# Shore_Power.net
KiCad netlist of a schematic drawn in Altium Designer
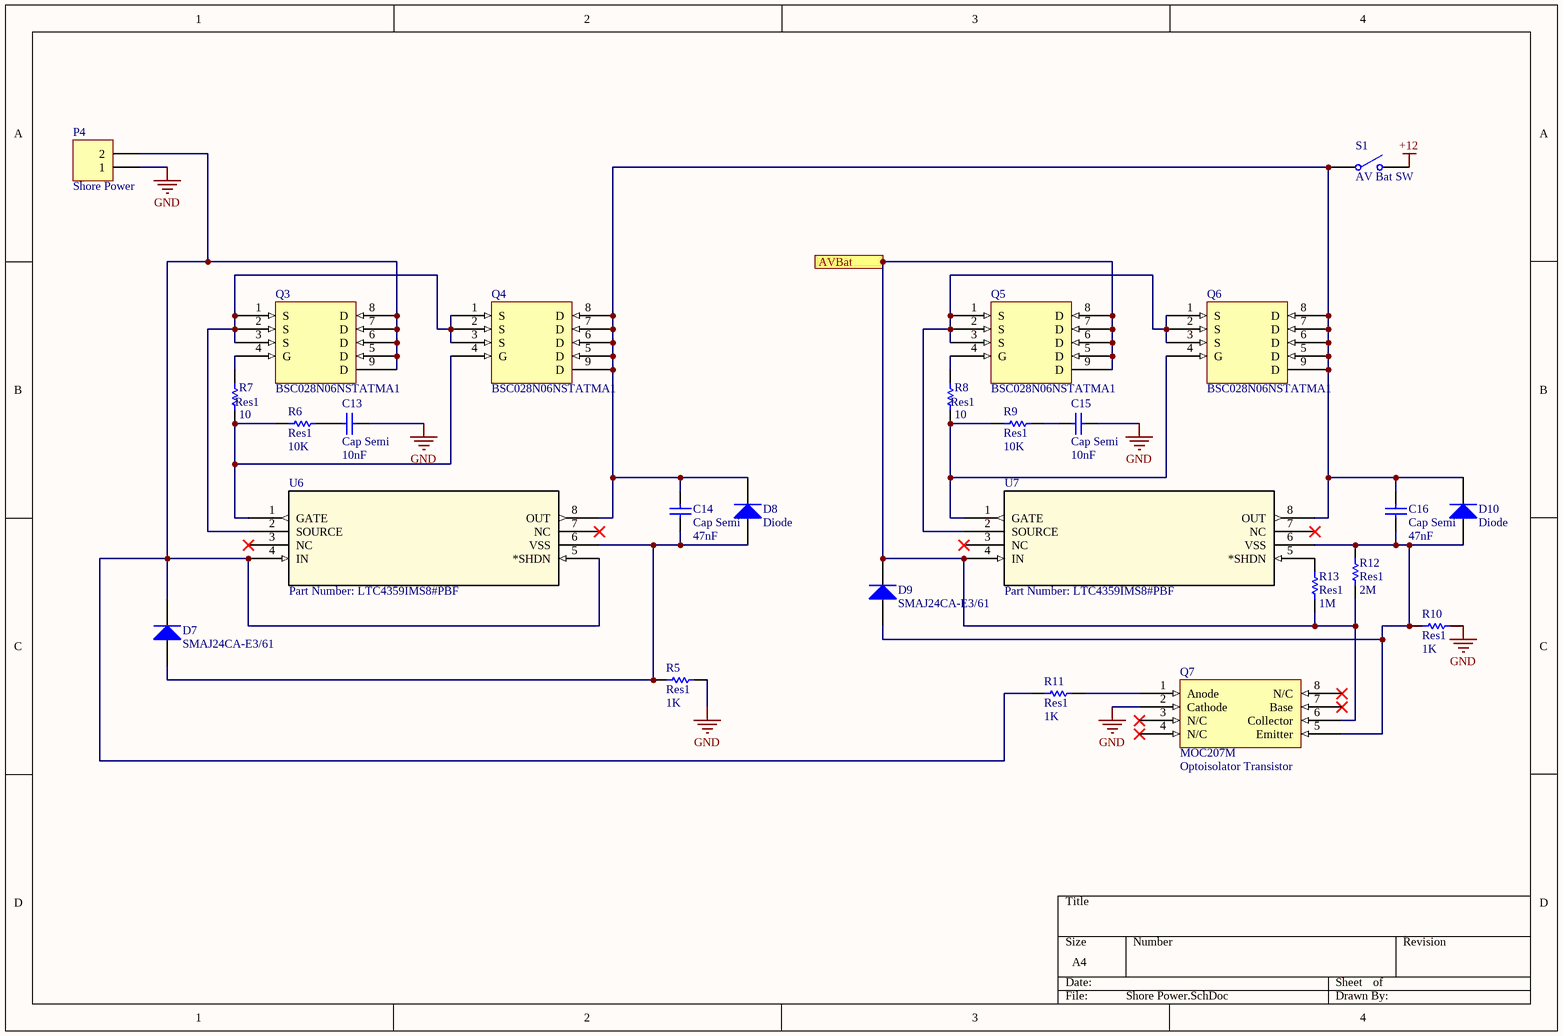
[diagram p0: Shore Power.SchDoc]

(export (version "E")
  (design (tool "Eeschema 10.0.6"))
  (components
    (comp (ref "C13")
      (value "Cap Semi")
      (footprint "C1206")
      (description "Capacitor (Semiconductor SIM Model)")
      (fields (field (name "ALTIUM_VALUE") "10nF") (field (name "PUBLISHER") "Altium Limited"))
      (libsource (lib "Miscellaneous Devices") (part "Cap Semi"))
    )
    (comp (ref "C14")
      (value "Cap Semi")
      (footprint "C1206")
      (description "Capacitor (Semiconductor SIM Model)")
      (fields (field (name "ALTIUM_VALUE") "47nF") (field (name "PUBLISHER") "Altium Limited"))
      (libsource (lib "Miscellaneous Devices") (part "Cap Semi"))
    )
    (comp (ref "C15")
      (value "Cap Semi")
      (footprint "C1206")
      (description "Capacitor (Semiconductor SIM Model)")
      (fields (field (name "ALTIUM_VALUE") "10nF") (field (name "PUBLISHER") "Altium Limited"))
      (libsource (lib "Miscellaneous Devices") (part "Cap Semi"))
    )
    (comp (ref "C16")
      (value "Cap Semi")
      (footprint "C1206")
      (description "Capacitor (Semiconductor SIM Model)")
      (fields (field (name "ALTIUM_VALUE") "47nF") (field (name "PUBLISHER") "Altium Limited"))
      (libsource (lib "Miscellaneous Devices") (part "Cap Semi"))
    )
    (comp (ref "D7")
      (value "SMAJ24CA-E3/61")
      (footprint "DIODE_DO-214AC")
      (description "Default Diode")
      (fields (field (name "PUBLISHER") "Altium Limited"))
      (libsource (lib "Miscellaneous Devices") (part "Diode"))
    )
    (comp (ref "D8")
      (value "Diode")
      (footprint "DIOM4427X27N")
      (description "Default Diode")
      (fields (field (name "PUBLISHER") "Altium Limited"))
      (libsource (lib "Miscellaneous Devices") (part "Diode"))
    )
    (comp (ref "D9")
      (value "SMAJ24CA-E3/61")
      (footprint "DIODE_DO-214AC")
      (description "Default Diode")
      (fields (field (name "PUBLISHER") "Altium Limited"))
      (libsource (lib "Miscellaneous Devices") (part "Diode"))
    )
    (comp (ref "D10")
      (value "Diode")
      (footprint "DIOM4427X27N")
      (description "Default Diode")
      (fields (field (name "PUBLISHER") "Altium Limited"))
      (libsource (lib "Miscellaneous Devices") (part "Diode"))
    )
    (comp (ref "P4")
      (value "Shore Power")
      (footprint "HDR1X2")
      (description "Header, 2-Pin")
      (fields (field (name "PUBLISHER") "Altium Limited"))
      (libsource (lib "Miscellaneous Connectors") (part "Header 2"))
    )
    (comp (ref "Q3")
      (value "BSC028N06NSTATMA1")
      (footprint "FDMS86101A")
      (description "MOSFET N-CH 100V 13A POWER56")
      (libsource (lib "FDMS86101A") (part "FDMS86101A"))
    )
    (comp (ref "Q4")
      (value "BSC028N06NSTATMA1")
      (footprint "FDMS86101A")
      (description "MOSFET N-CH 100V 13A POWER56")
      (libsource (lib "FDMS86101A") (part "FDMS86101A"))
    )
    (comp (ref "Q5")
      (value "BSC028N06NSTATMA1")
      (footprint "FDMS86101A")
      (description "MOSFET N-CH 100V 13A POWER56")
      (libsource (lib "FDMS86101A") (part "FDMS86101A"))
    )
    (comp (ref "Q6")
      (value "BSC028N06NSTATMA1")
      (footprint "FDMS86101A")
      (description "MOSFET N-CH 100V 13A POWER56")
      (libsource (lib "FDMS86101A") (part "FDMS86101A"))
    )
    (comp (ref "Q7")
      (value "MOC207M")
      (footprint "SOIC127P590X363-8N")
      (description "Optoisolator Transistor")
      (fields (field (name "DESC") "Optoisolator Transistor"))
      (libsource (lib "MOC207M") (part "MOC207M"))
    )
    (comp (ref "R5")
      (value "Res1")
      (footprint "STA_RMCF2512")
      (description "Resistor")
      (fields (field (name "ALTIUM_VALUE") "1K") (field (name "PUBLISHER") "Altium Limited"))
      (libsource (lib "Miscellaneous Devices") (part "Res1"))
    )
    (comp (ref "R6")
      (value "Res1")
      (footprint "6-0805_L")
      (description "Resistor")
      (fields (field (name "ALTIUM_VALUE") "10K") (field (name "PUBLISHER") "Altium Limited"))
      (libsource (lib "Miscellaneous Devices") (part "Res1"))
    )
    (comp (ref "R7")
      (value "Res1")
      (footprint "6-0805_L")
      (description "Resistor")
      (fields (field (name "ALTIUM_VALUE") "10") (field (name "PUBLISHER") "Altium Limited"))
      (libsource (lib "Miscellaneous Devices") (part "Res1"))
    )
    (comp (ref "R8")
      (value "Res1")
      (footprint "6-0805_L")
      (description "Resistor")
      (fields (field (name "ALTIUM_VALUE") "10") (field (name "PUBLISHER") "Altium Limited"))
      (libsource (lib "Miscellaneous Devices") (part "Res1"))
    )
    (comp (ref "R9")
      (value "Res1")
      (footprint "6-0805_L")
      (description "Resistor")
      (fields (field (name "ALTIUM_VALUE") "10K") (field (name "PUBLISHER") "Altium Limited"))
      (libsource (lib "Miscellaneous Devices") (part "Res1"))
    )
    (comp (ref "R10")
      (value "Res1")
      (footprint "STA_RMCF2512")
      (description "Resistor")
      (fields (field (name "ALTIUM_VALUE") "1K") (field (name "PUBLISHER") "Altium Limited"))
      (libsource (lib "Miscellaneous Devices") (part "Res1"))
    )
    (comp (ref "R11")
      (value "Res1")
      (footprint "STA_RMCF2512")
      (description "Resistor")
      (fields (field (name "ALTIUM_VALUE") "1K") (field (name "PUBLISHER") "Altium Limited"))
      (libsource (lib "Miscellaneous Devices") (part "Res1"))
    )
    (comp (ref "R12")
      (value "Res1")
      (footprint "J1-0603")
      (description "Resistor")
      (fields (field (name "ALTIUM_VALUE") "2M") (field (name "PUBLISHER") "Altium Limited"))
      (libsource (lib "Miscellaneous Devices") (part "Res1"))
    )
    (comp (ref "R13")
      (value "Res1")
      (footprint "J1-0603")
      (description "Resistor")
      (fields (field (name "ALTIUM_VALUE") "1M") (field (name "PUBLISHER") "Altium Limited"))
      (libsource (lib "Miscellaneous Devices") (part "Res1"))
    )
    (comp (ref "S1")
      (value "AV Bat SW")
      (footprint "SPST-2")
      (description "Single-Pole, Single-Throw Switch")
      (fields (field (name "PUBLISHER") "Altium Limited"))
      (libsource (lib "Miscellaneous Devices") (part "SW-SPST"))
    )
    (comp (ref "U6")
      (value "Part Number: LTC4359IMS8#PBF")
      (footprint "MSOP-8_MS")
      (description "No Description Available")
      (fields
        (field (name "MANUFACTURER_PART_NUMBER") "LTC4359IMS8#PBF")
        (field (name "COPYRIGHT") "Copyright (C) 2018 Accelerated Designs. All rights reserved")
      )
      (libsource (lib "LTC4359IMS8#PBF") (part "LTC4359IMS8#PBF"))
    )
    (comp (ref "U7")
      (value "Part Number: LTC4359IMS8#PBF")
      (footprint "MSOP-8_MS")
      (description "No Description Available")
      (fields
        (field (name "MANUFACTURER_PART_NUMBER") "LTC4359IMS8#PBF")
        (field (name "COPYRIGHT") "Copyright (C) 2018 Accelerated Designs. All rights reserved")
      )
      (libsource (lib "LTC4359IMS8#PBF") (part "LTC4359IMS8#PBF"))
    )
  )
  (nets
    (net (code "1") (name "+12") (class "Default")
      (node (ref "S1") (pin "2") (pinfunction "NO_2") (pintype "passive"))
    )
    (net (code "2") (name "/AVBat") (class "Default")
      (node (ref "D9") (pin "2") (pinfunction "K_2") (pintype "passive"))
      (node (ref "Q5") (pin "5") (pinfunction "D_5") (pintype "input"))
      (node (ref "Q5") (pin "6") (pinfunction "D_6") (pintype "input"))
      (node (ref "Q5") (pin "7") (pinfunction "D_7") (pintype "input"))
      (node (ref "Q5") (pin "8") (pinfunction "D_8") (pintype "input"))
      (node (ref "Q5") (pin "9") (pinfunction "D_9") (pintype "passive"))
      (node (ref "Q7") (pin "6") (pinfunction "Collector_6") (pintype "input"))
      (node (ref "R12") (pin "1") (pinfunction "1_1") (pintype "passive"))
      (node (ref "R13") (pin "2") (pinfunction "2_2") (pintype "passive"))
      (node (ref "U7") (pin "4") (pinfunction "IN_4") (pintype "input"))
    )
    (net (code "3") (name "GND") (class "Default")
      (node (ref "C13") (pin "1") (pinfunction "1_1") (pintype "passive"))
      (node (ref "C15") (pin "1") (pinfunction "1_1") (pintype "passive"))
      (node (ref "P4") (pin "1") (pinfunction "1_1") (pintype "passive"))
      (node (ref "Q7") (pin "2") (pinfunction "Cathode_2") (pintype "input"))
      (node (ref "R10") (pin "1") (pinfunction "1_1") (pintype "passive"))
      (node (ref "R5") (pin "1") (pinfunction "1_1") (pintype "passive"))
    )
    (net (code "4") (name "Net-(C13-Pad2)") (class "Default")
      (node (ref "C13") (pin "2") (pinfunction "2_2") (pintype "passive"))
      (node (ref "R6") (pin "2") (pinfunction "2_2") (pintype "passive"))
    )
    (net (code "5") (name "Net-(C15-Pad2)") (class "Default")
      (node (ref "C15") (pin "2") (pinfunction "2_2") (pintype "passive"))
      (node (ref "R9") (pin "2") (pinfunction "2_2") (pintype "passive"))
    )
    (net (code "6") (name "Net-(D7-A)") (class "Default")
      (node (ref "C14") (pin "2") (pinfunction "2_2") (pintype "passive"))
      (node (ref "D7") (pin "1") (pinfunction "A_1") (pintype "passive"))
      (node (ref "D8") (pin "1") (pinfunction "A_1") (pintype "passive"))
      (node (ref "R5") (pin "2") (pinfunction "2_2") (pintype "passive"))
      (node (ref "U6") (pin "6") (pinfunction "VSS_6") (pintype "power_in"))
    )
    (net (code "7") (name "Net-(D7-K)") (class "Default")
      (node (ref "D7") (pin "2") (pinfunction "K_2") (pintype "passive"))
      (node (ref "P4") (pin "2") (pinfunction "2_2") (pintype "passive"))
      (node (ref "Q3") (pin "5") (pinfunction "D_5") (pintype "input"))
      (node (ref "Q3") (pin "6") (pinfunction "D_6") (pintype "input"))
      (node (ref "Q3") (pin "7") (pinfunction "D_7") (pintype "input"))
      (node (ref "Q3") (pin "8") (pinfunction "D_8") (pintype "input"))
      (node (ref "Q3") (pin "9") (pinfunction "D_9") (pintype "passive"))
      (node (ref "R11") (pin "2") (pinfunction "2_2") (pintype "passive"))
      (node (ref "U6") (pin "4") (pinfunction "IN_4") (pintype "input"))
      (node (ref "U6") (pin "5") (pinfunction "*SHDN_5") (pintype "input"))
    )
    (net (code "8") (name "Net-(D10-A)") (class "Default")
      (node (ref "C16") (pin "2") (pinfunction "2_2") (pintype "passive"))
      (node (ref "D10") (pin "1") (pinfunction "A_1") (pintype "passive"))
      (node (ref "D9") (pin "1") (pinfunction "A_1") (pintype "passive"))
      (node (ref "Q7") (pin "5") (pinfunction "Emitter_5") (pintype "input"))
      (node (ref "R10") (pin "2") (pinfunction "2_2") (pintype "passive"))
      (node (ref "R12") (pin "2") (pinfunction "2_2") (pintype "passive"))
      (node (ref "U7") (pin "6") (pinfunction "VSS_6") (pintype "power_in"))
    )
    (net (code "9") (name "Net-(D10-K)") (class "Default")
      (node (ref "C14") (pin "1") (pinfunction "1_1") (pintype "passive"))
      (node (ref "C16") (pin "1") (pinfunction "1_1") (pintype "passive"))
      (node (ref "D10") (pin "2") (pinfunction "K_2") (pintype "passive"))
      (node (ref "D8") (pin "2") (pinfunction "K_2") (pintype "passive"))
      (node (ref "Q4") (pin "5") (pinfunction "D_5") (pintype "input"))
      (node (ref "Q4") (pin "6") (pinfunction "D_6") (pintype "input"))
      (node (ref "Q4") (pin "7") (pinfunction "D_7") (pintype "input"))
      (node (ref "Q4") (pin "8") (pinfunction "D_8") (pintype "input"))
      (node (ref "Q4") (pin "9") (pinfunction "D_9") (pintype "passive"))
      (node (ref "Q6") (pin "5") (pinfunction "D_5") (pintype "input"))
      (node (ref "Q6") (pin "6") (pinfunction "D_6") (pintype "input"))
      (node (ref "Q6") (pin "7") (pinfunction "D_7") (pintype "input"))
      (node (ref "Q6") (pin "8") (pinfunction "D_8") (pintype "input"))
      (node (ref "Q6") (pin "9") (pinfunction "D_9") (pintype "passive"))
      (node (ref "S1") (pin "1") (pinfunction "COMMON_1") (pintype "passive"))
      (node (ref "U6") (pin "8") (pinfunction "OUT_8") (pintype "output"))
      (node (ref "U7") (pin "8") (pinfunction "OUT_8") (pintype "output"))
    )
    (net (code "10") (name "Net-(Q3-G)") (class "Default")
      (node (ref "Q3") (pin "4") (pinfunction "G_4") (pintype "input"))
      (node (ref "R7") (pin "2") (pinfunction "2_2") (pintype "passive"))
    )
    (net (code "11") (name "Net-(Q4-G)") (class "Default")
      (node (ref "Q4") (pin "4") (pinfunction "G_4") (pintype "input"))
      (node (ref "R6") (pin "1") (pinfunction "1_1") (pintype "passive"))
      (node (ref "R7") (pin "1") (pinfunction "1_1") (pintype "passive"))
      (node (ref "U6") (pin "1") (pinfunction "GATE_1") (pintype "output"))
    )
    (net (code "12") (name "Net-(Q5-G)") (class "Default")
      (node (ref "Q5") (pin "4") (pinfunction "G_4") (pintype "input"))
      (node (ref "R8") (pin "2") (pinfunction "2_2") (pintype "passive"))
    )
    (net (code "13") (name "Net-(Q6-G)") (class "Default")
      (node (ref "Q6") (pin "4") (pinfunction "G_4") (pintype "input"))
      (node (ref "R8") (pin "1") (pinfunction "1_1") (pintype "passive"))
      (node (ref "R9") (pin "1") (pinfunction "1_1") (pintype "passive"))
      (node (ref "U7") (pin "1") (pinfunction "GATE_1") (pintype "output"))
    )
    (net (code "14") (name "Net-(Q7-Anode)") (class "Default")
      (node (ref "Q7") (pin "1") (pinfunction "Anode_1") (pintype "input"))
      (node (ref "R11") (pin "1") (pinfunction "1_1") (pintype "passive"))
    )
    (net (code "15") (name "Net-(U6-SOURCE)") (class "Default")
      (node (ref "Q3") (pin "1") (pinfunction "S_1") (pintype "input"))
      (node (ref "Q3") (pin "2") (pinfunction "S_2") (pintype "input"))
      (node (ref "Q3") (pin "3") (pinfunction "S_3") (pintype "input"))
      (node (ref "Q4") (pin "1") (pinfunction "S_1") (pintype "input"))
      (node (ref "Q4") (pin "2") (pinfunction "S_2") (pintype "input"))
      (node (ref "Q4") (pin "3") (pinfunction "S_3") (pintype "input"))
      (node (ref "U6") (pin "2") (pinfunction "SOURCE_2") (pintype "passive"))
    )
    (net (code "16") (name "Net-(U7-*SHDN)") (class "Default")
      (node (ref "R13") (pin "1") (pinfunction "1_1") (pintype "passive"))
      (node (ref "U7") (pin "5") (pinfunction "*SHDN_5") (pintype "input"))
    )
    (net (code "17") (name "Net-(U7-SOURCE)") (class "Default")
      (node (ref "Q5") (pin "1") (pinfunction "S_1") (pintype "input"))
      (node (ref "Q5") (pin "2") (pinfunction "S_2") (pintype "input"))
      (node (ref "Q5") (pin "3") (pinfunction "S_3") (pintype "input"))
      (node (ref "Q6") (pin "1") (pinfunction "S_1") (pintype "input"))
      (node (ref "Q6") (pin "2") (pinfunction "S_2") (pintype "input"))
      (node (ref "Q6") (pin "3") (pinfunction "S_3") (pintype "input"))
      (node (ref "U7") (pin "2") (pinfunction "SOURCE_2") (pintype "passive"))
    )
    (net (code "18") (name "unconnected-(Q7-Base-Pad7)") (class "Default")
      (node (ref "Q7") (pin "7") (pinfunction "Base_7") (pintype "input+no_connect"))
    )
    (net (code "19") (name "unconnected-(Q7-N{slash}C-Pad3)") (class "Default")
      (node (ref "Q7") (pin "3") (pinfunction "N/C_3") (pintype "input+no_connect"))
    )
    (net (code "20") (name "unconnected-(Q7-N{slash}C-Pad4)") (class "Default")
      (node (ref "Q7") (pin "4") (pinfunction "N/C_4") (pintype "input+no_connect"))
    )
    (net (code "21") (name "unconnected-(Q7-N{slash}C-Pad8)") (class "Default")
      (node (ref "Q7") (pin "8") (pinfunction "N/C_8") (pintype "input+no_connect"))
    )
    (net (code "22") (name "unconnected-(U6-NC-Pad3)") (class "Default")
      (node (ref "U6") (pin "3") (pinfunction "NC_3") (pintype "passive+no_connect"))
    )
    (net (code "23") (name "unconnected-(U6-NC-Pad7)") (class "Default")
      (node (ref "U6") (pin "7") (pinfunction "NC_7") (pintype "passive+no_connect"))
    )
    (net (code "24") (name "unconnected-(U7-NC-Pad3)") (class "Default")
      (node (ref "U7") (pin "3") (pinfunction "NC_3") (pintype "passive+no_connect"))
    )
    (net (code "25") (name "unconnected-(U7-NC-Pad7)") (class "Default")
      (node (ref "U7") (pin "7") (pinfunction "NC_7") (pintype "passive+no_connect"))
    )
  )
)
